# VDivider.net
KiCad netlist of a schematic drawn in EAGLE
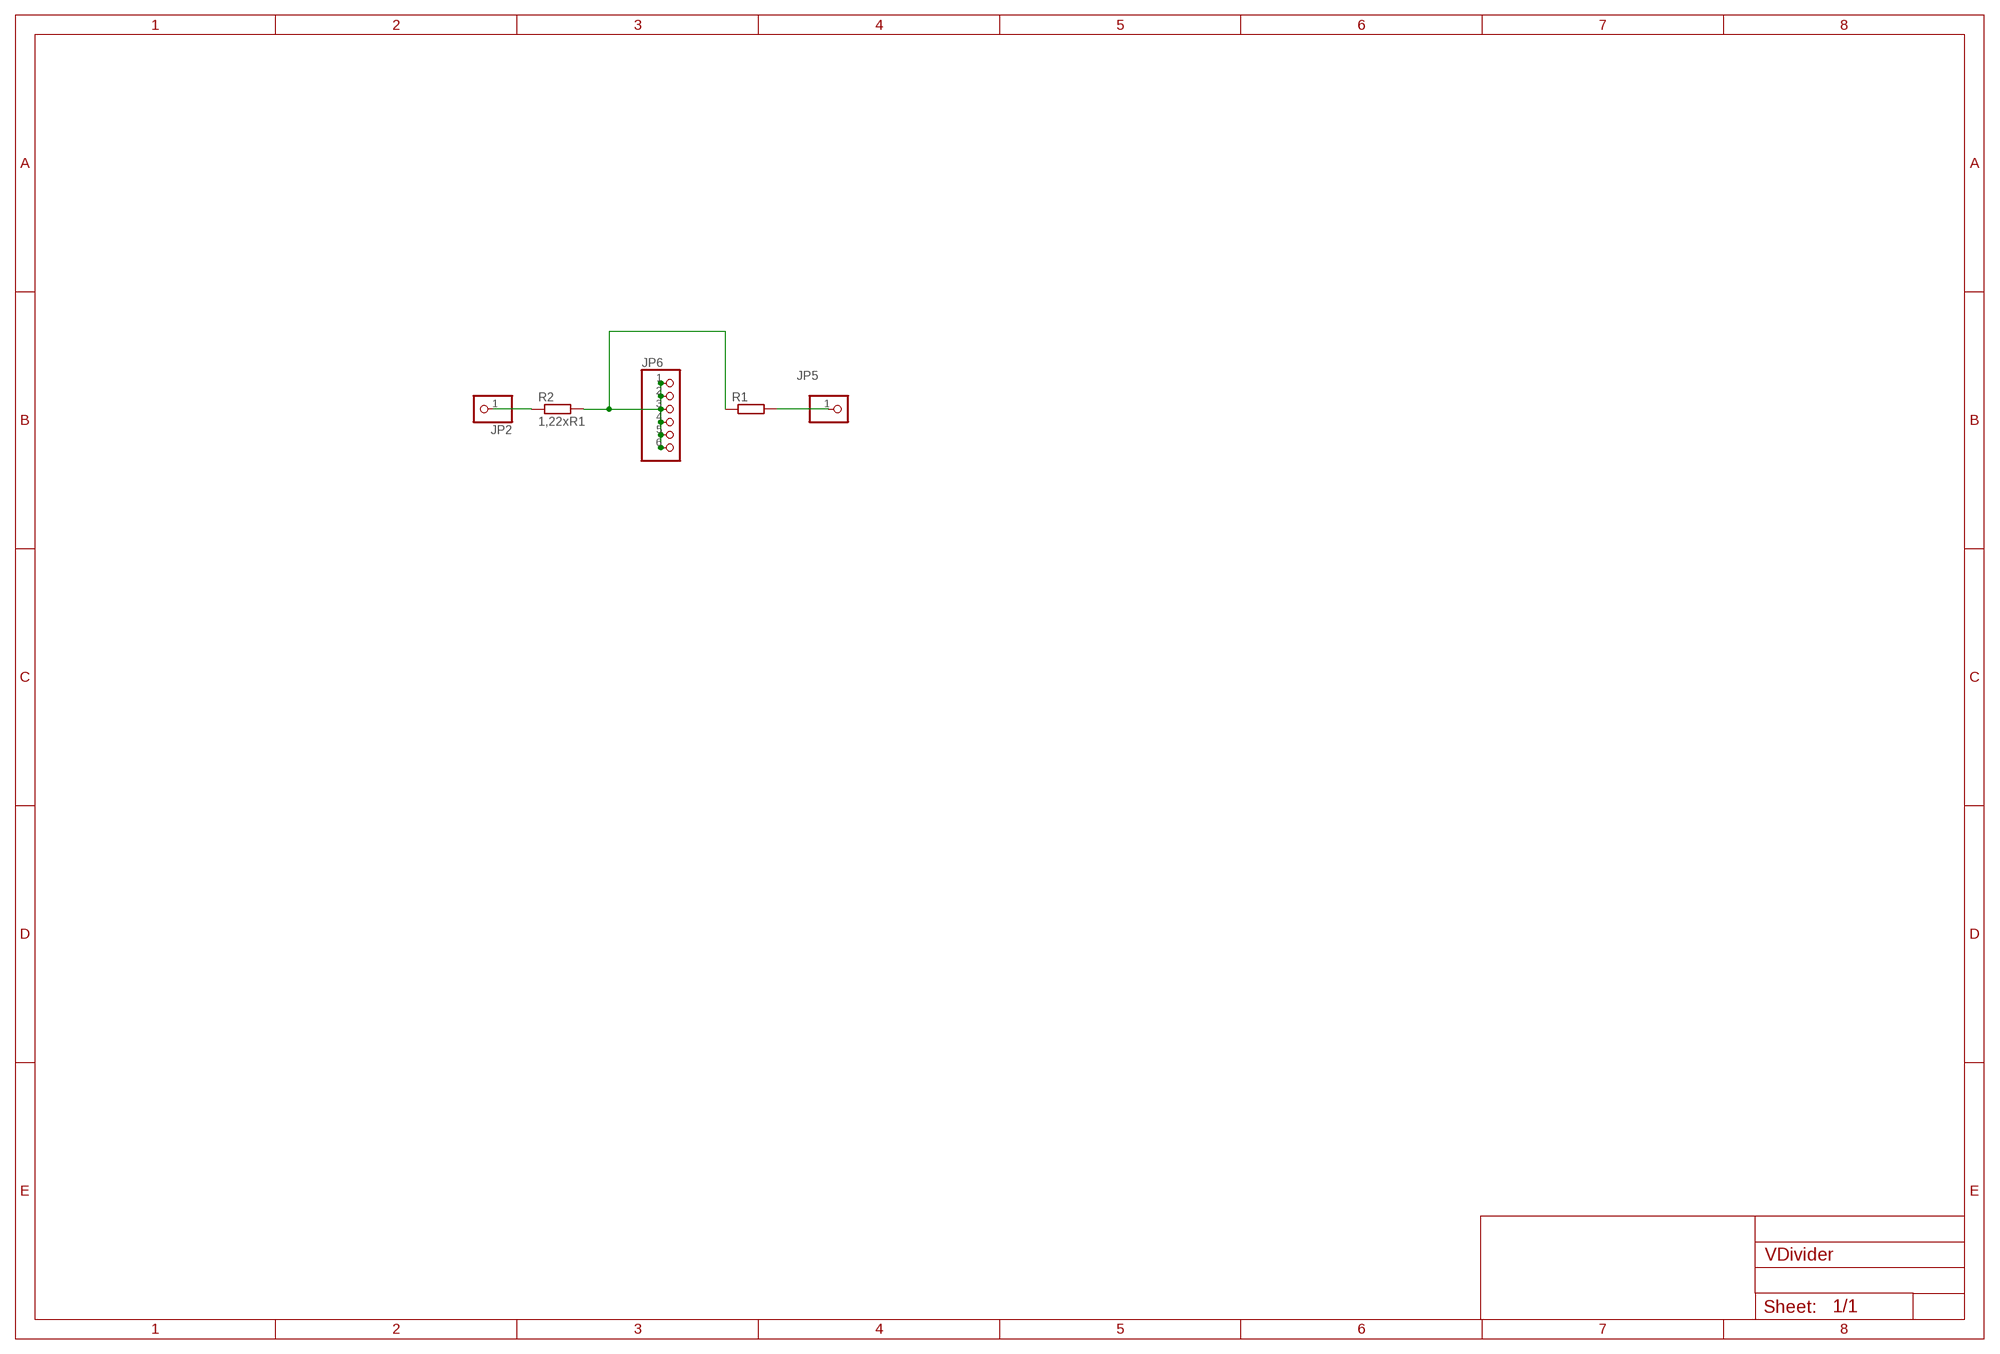
[diagram p0: schematic, sheet 1]

(export (version "E")
  (design (tool "Eeschema 10.0.6"))
  (components
    (comp (ref "JP2")
      (value "PINHD-1X1")
      (footprint "eagle-import:1X01")
      (libsource (lib "eagle-import") (part "PINHD-1X1"))
    )
    (comp (ref "JP5")
      (value "PINHD-1X1")
      (footprint "eagle-import:1X01")
      (libsource (lib "eagle-import") (part "PINHD-1X1"))
    )
    (comp (ref "JP6")
      (value "PINHD-1X6")
      (footprint "eagle-import:1X06")
      (libsource (lib "eagle-import") (part "PINHD-1X6"))
    )
    (comp (ref "R1")
      (value "R-EU_0204/7")
      (footprint "eagle-import:0204_7")
      (libsource (lib "eagle-import") (part "R-EU_0204/7"))
    )
    (comp (ref "R2")
      (value "1,22xR1")
      (footprint "eagle-import:0204_7")
      (libsource (lib "eagle-import") (part "R-EU_0204/7"))
    )
  )
  (nets
    (net (code "1") (name "Net-(JP2-Pad1)") (class "Default")
      (node (ref "JP2") (pin "1") (pinfunction "1_1") (pintype "passive"))
      (node (ref "R2") (pin "1") (pinfunction "1_1") (pintype "passive"))
    )
    (net (code "2") (name "Net-(JP5-Pad1)") (class "Default")
      (node (ref "JP5") (pin "1") (pinfunction "1_1") (pintype "passive"))
      (node (ref "R1") (pin "2") (pinfunction "2_2") (pintype "passive"))
    )
    (net (code "3") (name "Net-(JP6-Pad1)") (class "Default")
      (node (ref "JP6") (pin "1") (pinfunction "1_1") (pintype "passive"))
      (node (ref "JP6") (pin "2") (pinfunction "2_2") (pintype "passive"))
      (node (ref "JP6") (pin "3") (pinfunction "3_3") (pintype "passive"))
      (node (ref "JP6") (pin "4") (pinfunction "4_4") (pintype "passive"))
      (node (ref "JP6") (pin "5") (pinfunction "5_5") (pintype "passive"))
      (node (ref "JP6") (pin "6") (pinfunction "6_6") (pintype "passive"))
      (node (ref "R1") (pin "1") (pinfunction "1_1") (pintype "passive"))
      (node (ref "R2") (pin "2") (pinfunction "2_2") (pintype "passive"))
    )
  )
)
